# SCH_HackerCardV2_2025-07-10_1.net
KiCad netlist of a schematic drawn in EasyEDA
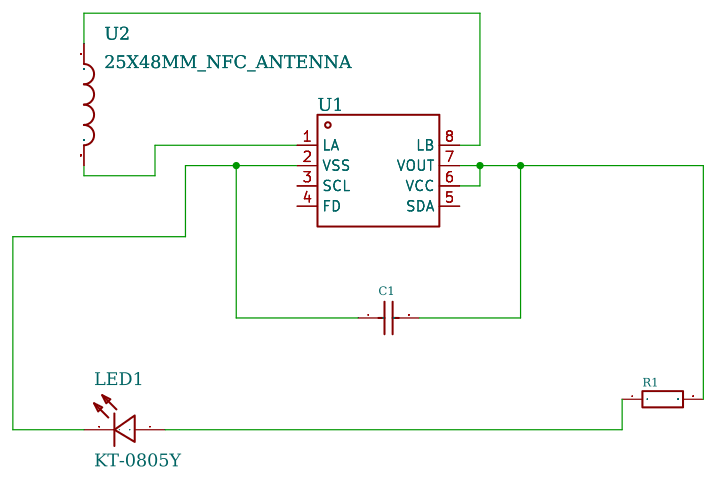
[diagram p0: schematic sheet]

(export (version "E")
  (design (tool "Eeschema 10.0.6"))
  (components
    (comp (ref "C1")
      (value "220nF")
      (fields
        (field (name "Manufacturer Part") "CL21B224KBFNNNE")
        (field (name "Manufacturer") "SAMSUNG(三星)")
      )
      (libsource (lib "") (part "Unknown_575_-460"))
    )
    (comp (ref "LED1")
      (value "KT-0805Y")
      (fields (field (name "Manufacturer") "KENTO"))
      (libsource (lib "") (part "Unknown_445_-405"))
    )
    (comp (ref "R1")
      (value "47Ω")
      (fields
        (field (name "Manufacturer Part") "0603WAF470JT5E")
        (field (name "Manufacturer") "UNI-ROYAL(厚声)")
      )
      (libsource (lib "") (part "Unknown_710_-420"))
    )
    (comp (ref "U1")
      (value "13.56MHz")
      (fields (field (name "Manufacturer Part") "NT3H2111W0FHKH") (field (name "Manufacturer") "NXP(恩智浦)"))
      (libsource (lib "") (part "Unknown_570_-530"))
    )
    (comp (ref "U2") (value "25X48MM_NFC_ANTENNA") (libsource (lib "") (part "Unknown_425_-565")))
  )
  (nets
    (net (code "1") (name "Net-(LED1-+)") (class "Default")
      (node (ref "LED1") (pin "1") (pinfunction "+_1") (pintype "unspecified"))
      (node (ref "R1") (pin "1") (pinfunction "1_1") (pintype "unspecified"))
    )
    (net (code "2") (name "Net-(LED1--)") (class "Default")
      (node (ref "C1") (pin "1") (pinfunction "1_1") (pintype "unspecified"))
      (node (ref "LED1") (pin "2") (pinfunction "-_2") (pintype "unspecified"))
      (node (ref "U1") (pin "2") (pinfunction "VSS_2") (pintype "unspecified"))
    )
    (net (code "3") (name "Net-(U1-LA)") (class "Default")
      (node (ref "U1") (pin "1") (pinfunction "LA_1") (pintype "unspecified"))
      (node (ref "U2") (pin "P$2") (pinfunction "P$2_P$2") (pintype "unspecified"))
    )
    (net (code "4") (name "Net-(U1-LB)") (class "Default")
      (node (ref "U1") (pin "8") (pinfunction "LB_8") (pintype "unspecified"))
      (node (ref "U2") (pin "P$1") (pinfunction "P$1_P$1") (pintype "unspecified"))
    )
    (net (code "5") (name "Net-(U1-VCC)") (class "Default")
      (node (ref "C1") (pin "2") (pinfunction "2_2") (pintype "unspecified"))
      (node (ref "R1") (pin "2") (pinfunction "2_2") (pintype "unspecified"))
      (node (ref "U1") (pin "6") (pinfunction "VCC_6") (pintype "unspecified"))
      (node (ref "U1") (pin "7") (pinfunction "VOUT_7") (pintype "unspecified"))
    )
    (net (code "6") (name "unconnected-(U1-FD-Pad4)") (class "Default")
      (node (ref "U1") (pin "4") (pinfunction "FD_4") (pintype "unspecified"))
    )
    (net (code "7") (name "unconnected-(U1-SCL-Pad3)") (class "Default")
      (node (ref "U1") (pin "3") (pinfunction "SCL_3") (pintype "unspecified"))
    )
    (net (code "8") (name "unconnected-(U1-SDA-Pad5)") (class "Default")
      (node (ref "U1") (pin "5") (pinfunction "SDA_5") (pintype "unspecified"))
    )
  )
)
